# COMMUNICATION_INTERFACE.net
KiCad netlist of a schematic drawn in Altium Designer
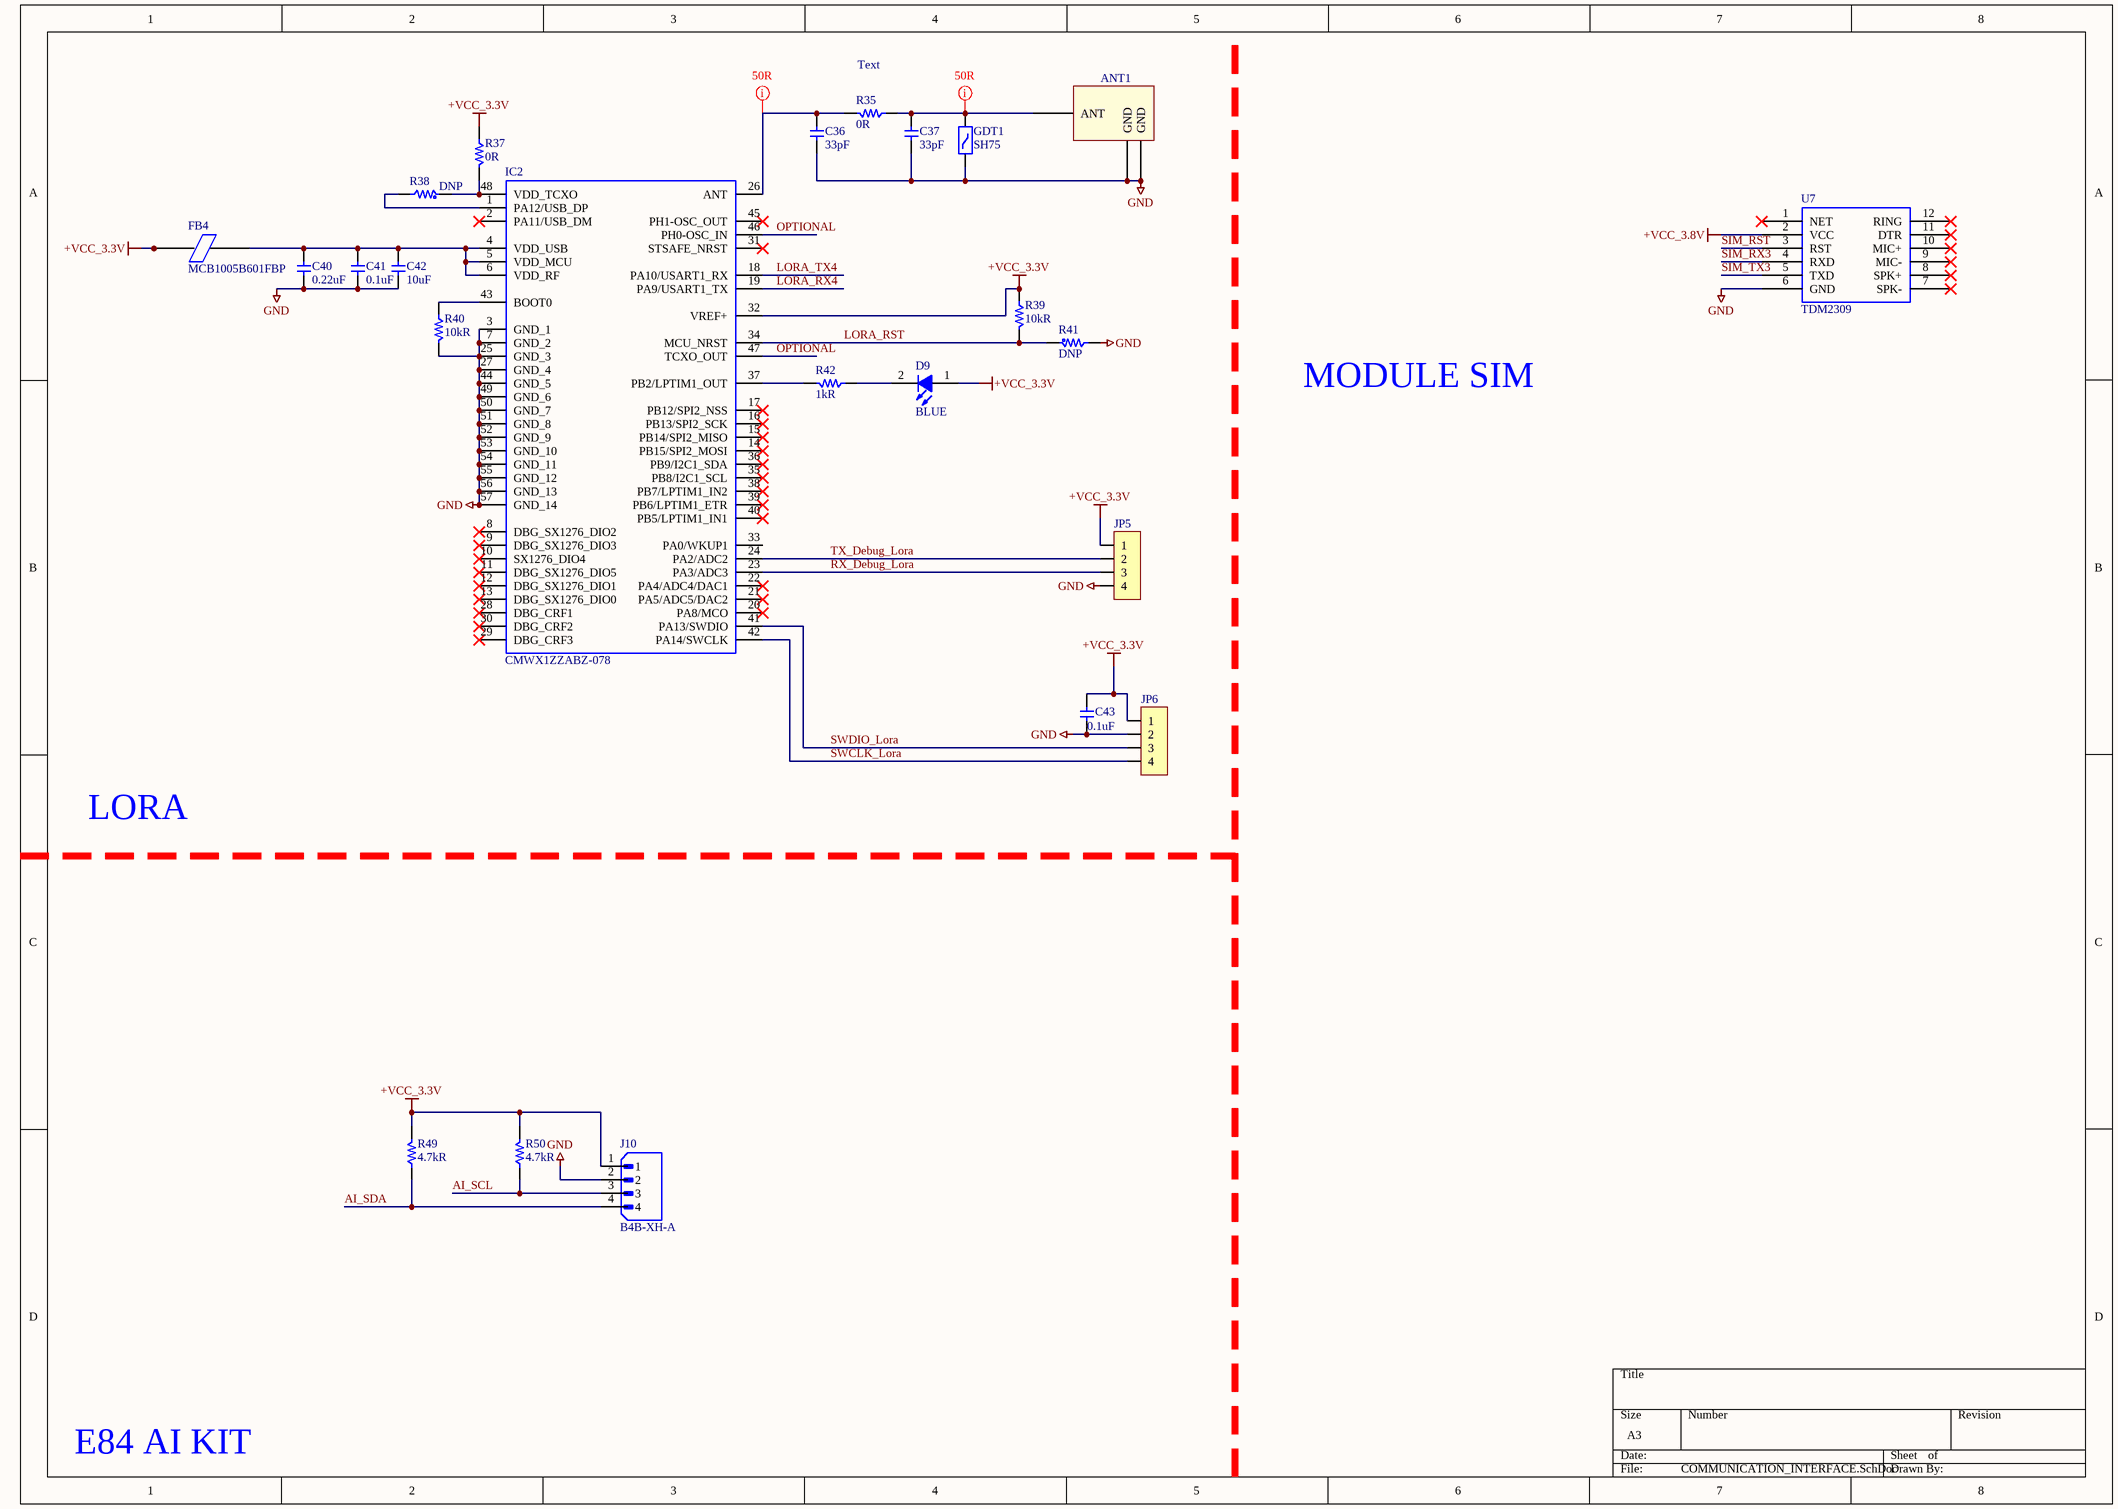
[diagram p0: COMMUNICATION_INTERFACE.SchDoc]

(export (version "E")
  (design (tool "Eeschema 10.0.6"))
  (components
    (comp (ref "ANT1")
      (value "Anten SMD")
      (footprint "20279-001E-01")
      (libsource (lib "BSR") (part "Antenna SMD"))
    )
    (comp (ref "C36")
      (value "33pF")
      (footprint "CAP 0402 (1005)")
      (description "50V 33pF NP0 ±5% 0402 Multilayer Ceramic Capacitors MLCC - SMD/SMT ROHS")
      (fields
        (field (name "MANUFACTURER") "YAGEO")
        (field (name "MANUFACTURER PART NUMBER") "CC0402JRNPO9BN330")
      )
      (libsource (lib "BSR NODE_V2.0 LIB") (part "CAP0402 33pF 50V"))
    )
    (comp (ref "C37")
      (value "33pF")
      (footprint "CAP 0402 (1005)")
      (description "50V 33pF NP0 ±5% 0402 Multilayer Ceramic Capacitors MLCC - SMD/SMT ROHS")
      (fields
        (field (name "MANUFACTURER") "YAGEO")
        (field (name "MANUFACTURER PART NUMBER") "CC0402JRNPO9BN330")
      )
      (libsource (lib "BSR NODE_V2.0 LIB") (part "CAP0402 33pF 50V"))
    )
    (comp (ref "C40")
      (value "0.22uF")
      (footprint "CAP 0402 (1005)")
      (description "35V 0.22uF X5R ±10% 0402 Multilayer Ceramic Capacitors MLCC - SMD/SMT ROHS")
      (fields
        (field (name "MANUFACTURER") "Murata Electronics")
        (field (name "MANUFACTURER PART NUMBER") "GRT155R6YA224KE01D")
      )
      (libsource (lib "BSR NODE_V2.0 LIB") (part "CAP0402 0.22uF 35V"))
    )
    (comp (ref "C41")
      (value "0.1uF")
      (footprint "CAP 0402 (1005)")
      (description "50V 100nF ±10% 0402 Multilayer Ceramic Capacitors MLCC - SMD/SMT ROHS")
      (fields
        (field (name "MANUFACTURER") "Samwha Capacitor")
        (field (name "MANUFACTURER PART NUMBER") "CS1005X7R104K500NR")
      )
      (libsource (lib "BSR NODE_V2.0 LIB") (part "CAP0402 0.1uF 50V"))
    )
    (comp (ref "C42")
      (value "10uF")
      (footprint "CAP 0603 (1608)")
      (description "25V 10uF X5R ±20% 0603 Multilayer Ceramic Capacitors MLCC - SMD/SMT ROHS")
      (fields
        (field (name "MANUFACTURER") "Chinocera")
        (field (name "MANUFACTURER PART NUMBER") "HGC0603R5106M250NTHJ")
      )
      (libsource (lib "BSR NODE_V2.0 LIB") (part "CAP0603 10uF 25V"))
    )
    (comp (ref "C43")
      (value "0.1uF")
      (footprint "CAP 0402 (1005)")
      (description "50V 100nF ±10% 0402 Multilayer Ceramic Capacitors MLCC - SMD/SMT ROHS")
      (fields
        (field (name "MANUFACTURER") "Samwha Capacitor")
        (field (name "MANUFACTURER PART NUMBER") "CS1005X7R104K500NR")
      )
      (libsource (lib "BSR NODE_V2.0 LIB") (part "CAP0402 0.1uF 50V"))
    )
    (comp (ref "D9")
      (value "BLUE")
      (footprint "LED0402 BLUE")
      (description "blue 0402 Light Emitting Diodes (LED) ROHS")
      (fields
        (field (name "MANUFACTURER") "BrtLed(Bright LED Elec)")
        (field (name "MANUFACTURER PART NUMBER") "BL-HB337A-AV-TRB")
      )
      (libsource (lib "BSR NODE_V2.0 LIB") (part "LED BLUE 0402"))
    )
    (comp (ref "FB4")
      (value "MCB1005B601FBP")
      (footprint "FB 0402 (1005)")
      (description "600mΩ ±25% 600Ω@100MHz 0402 Ferrite Beads ROHS")
      (fields (field (name "MANUFACTURER") "INPAQ"))
      (libsource (lib "BSR NODE_V2.0 LIB") (part "MCB1005B601FBP"))
    )
    (comp (ref "GDT1")
      (value "SH75")
      (footprint "GDT")
      (description "Gas Discharge Tube 75 V 5000A (5kA) 2 Pole Surface Mount")
      (fields (field (name "MANUFACTURER") "Littelfuse"))
      (libsource (lib "BSR NODE_V2.0 LIB") (part "GDT 75V 5KA 2 POLE SURFACE MOUNT"))
    )
    (comp (ref "IC2")
      (value "CMWX1ZZABZ-078")
      (footprint "CMWX1ZZABZ-078")
      (description "Integrated Circuit")
      (fields (field (name "MOUSER PART NUMBER") "81-CMWX1ZZABZ-078"))
      (libsource (lib "BSR") (part "CMWX1ZZABZ-078"))
    )
    (comp (ref "J10")
      (value "B4B-XH-A")
      (footprint "JST_B4B-XH-A")
      (description "Connector Header Through Hole 4 position 0.098 (2.50mm)")
      (fields (field (name "MF") "JST Sales"))
      (libsource (lib "B4B-XH-A") (part "B4B-XH-A"))
    )
    (comp (ref "JP5")
      (value "JP 1x4 2.54")
      (footprint "JP 1X4 DT")
      (description "Cắm")
      (libsource (lib "Altium_Lib_by_KhueNguyenCreator") (part "JP 1x4 2.54 Duc Thang"))
    )
    (comp (ref "JP6")
      (value "JP 1x4 2.54")
      (footprint "JP 1X4 DT")
      (description "Cắm")
      (libsource (lib "Altium_Lib_by_KhueNguyenCreator") (part "JP 1x4 2.54 Duc Thang"))
    )
    (comp (ref "R35")
      (value "0R")
      (footprint "RES 0603 (1608)")
      (description "0Ω 0603 Chip Resistor - Surface Mount ROHS")
      (fields
        (field (name "MANUFACTURER") "KOA Speer Elec")
        (field (name "MANUFACTURER PART NUMBER") "RK73Z1JTTD")
      )
      (libsource (lib "BSR NODE_V2.0 LIB") (part "RES0603 0R"))
    )
    (comp (ref "R37")
      (value "0R")
      (footprint "RES 0603 (1608)")
      (description "0Ω 0603 Chip Resistor - Surface Mount ROHS")
      (fields
        (field (name "MANUFACTURER") "KOA Speer Elec")
        (field (name "MANUFACTURER PART NUMBER") "RK73Z1JTTD")
      )
      (libsource (lib "BSR NODE_V2.0 LIB") (part "RES0603 0R"))
    )
    (comp (ref "R38")
      (value "DNP")
      (footprint "RES 0603 (1608)")
      (description "Res do not populate")
      (libsource (lib "BSR NODE_V2.0 LIB") (part "RES0603 DNP"))
    )
    (comp (ref "R39")
      (value "10kR")
      (footprint "RES 0402 (1005)")
      (description "±1% 10kΩ 0402 Chip Resistor - Surface Mount ROHS")
      (fields (field (name "MANUFACTURER") "VO") (field (name "MANUFACTURER PART NUMBER") "SCR0402F10K"))
      (libsource (lib "BSR NODE_V2.0 LIB") (part "RES0402 10kR 1%"))
    )
    (comp (ref "R40")
      (value "10kR")
      (footprint "RES 0402 (1005)")
      (description "±1% 10kΩ 0402 Chip Resistor - Surface Mount ROHS")
      (fields (field (name "MANUFACTURER") "VO") (field (name "MANUFACTURER PART NUMBER") "SCR0402F10K"))
      (libsource (lib "BSR NODE_V2.0 LIB") (part "RES0402 10kR 1%"))
    )
    (comp (ref "R41")
      (value "DNP")
      (footprint "RES 0402 (1005)")
      (description "Res do not populate")
      (libsource (lib "BSR NODE_V2.0 LIB") (part "RES0402 DNP"))
    )
    (comp (ref "R42")
      (value "1kR")
      (footprint "RES 0402 (1005)")
      (description "±5% 1kΩ 0402 Chip Resistor - Surface Mount ROHS")
      (fields (field (name "MANUFACTURER") "VO") (field (name "MANUFACTURER PART NUMBER") "SCR0402J1K"))
      (libsource (lib "BSR NODE_V2.0 LIB") (part "RES0402 1kR 1%"))
    )
    (comp (ref "R49")
      (value "4.7kR")
      (footprint "RES 0402 (1005)")
      (description "±5% 1kΩ 0402 Chip Resistor - Surface Mount ROHS")
      (fields (field (name "MANUFACTURER") "VO") (field (name "MANUFACTURER PART NUMBER") "SCR0402J1K"))
      (libsource (lib "BSR NODE_V2.0 LIB") (part "RES0402 1kR 1%"))
    )
    (comp (ref "R50")
      (value "4.7kR")
      (footprint "RES 0402 (1005)")
      (description "±5% 1kΩ 0402 Chip Resistor - Surface Mount ROHS")
      (fields (field (name "MANUFACTURER") "VO") (field (name "MANUFACTURER PART NUMBER") "SCR0402J1K"))
      (libsource (lib "BSR NODE_V2.0 LIB") (part "RES0402 1kR 1%"))
    )
    (comp (ref "U7")
      (value "TDM2309")
      (footprint "MODULE SIM SIM800L")
      (description "Module 4G SIMCOM A7680C TDM2309")
      (fields (field (name "MANUFACTURER") "SIMCOM"))
      (libsource (lib "BSR NODE_V2.0 LIB") (part "SIM TDM2309"))
    )
  )
  (nets
    (net (code "1") (name "+VCC_3.3V") (class "Default")
      (node (ref "C43") (pin "1") (pinfunction "1_1") (pintype "passive"))
      (node (ref "D9") (pin "1") (pinfunction "A_1") (pintype "passive"))
      (node (ref "FB4") (pin "1") (pinfunction "1_1") (pintype "passive"))
      (node (ref "IC2") (pin "32") (pinfunction "VREF+_32") (pintype "passive"))
      (node (ref "J10") (pin "1") (pinfunction "1_1") (pintype "passive"))
      (node (ref "JP5") (pin "1") (pinfunction "1_1") (pintype "passive"))
      (node (ref "JP6") (pin "1") (pinfunction "1_1") (pintype "passive"))
      (node (ref "R37") (pin "2") (pinfunction "2_2") (pintype "passive"))
      (node (ref "R39") (pin "2") (pinfunction "2_2") (pintype "passive"))
      (node (ref "R49") (pin "1") (pinfunction "1_1") (pintype "passive"))
      (node (ref "R50") (pin "1") (pinfunction "1_1") (pintype "passive"))
    )
    (net (code "2") (name "+VCC_3.8V") (class "Default")
      (node (ref "U7") (pin "2") (pinfunction "VCC_2") (pintype "passive"))
    )
    (net (code "3") (name "/AI_SCL") (class "Default")
      (node (ref "J10") (pin "3") (pinfunction "3_3") (pintype "passive"))
      (node (ref "R50") (pin "2") (pinfunction "2_2") (pintype "passive"))
    )
    (net (code "4") (name "/AI_SDA") (class "Default")
      (node (ref "J10") (pin "4") (pinfunction "4_4") (pintype "passive"))
      (node (ref "R49") (pin "2") (pinfunction "2_2") (pintype "passive"))
    )
    (net (code "5") (name "/LORA_RST") (class "Default")
      (node (ref "IC2") (pin "34") (pinfunction "MCU_NRST_34") (pintype "passive"))
      (node (ref "R39") (pin "1") (pinfunction "1_1") (pintype "passive"))
      (node (ref "R41") (pin "1") (pinfunction "1_1") (pintype "passive"))
    )
    (net (code "6") (name "/LORA_RX4") (class "Default")
      (node (ref "IC2") (pin "19") (pinfunction "PA9/USART1_TX_19") (pintype "passive"))
    )
    (net (code "7") (name "/LORA_TX4") (class "Default")
      (node (ref "IC2") (pin "18") (pinfunction "PA10/USART1_RX_18") (pintype "passive"))
    )
    (net (code "8") (name "/OPTIONAL") (class "Default")
      (node (ref "IC2") (pin "46") (pinfunction "PH0-OSC_IN_46") (pintype "passive"))
      (node (ref "IC2") (pin "47") (pinfunction "TCXO_OUT_47") (pintype "passive"))
    )
    (net (code "9") (name "/RX_Debug_Lora") (class "Default")
      (node (ref "IC2") (pin "23") (pinfunction "PA3/ADC3_23") (pintype "passive"))
      (node (ref "JP5") (pin "3") (pinfunction "3_3") (pintype "passive"))
    )
    (net (code "10") (name "/SIM_RST") (class "Default")
      (node (ref "U7") (pin "3") (pinfunction "RST_3") (pintype "passive"))
    )
    (net (code "11") (name "/SIM_RX3") (class "Default")
      (node (ref "U7") (pin "4") (pinfunction "RXD_4") (pintype "passive"))
    )
    (net (code "12") (name "/SIM_TX3") (class "Default")
      (node (ref "U7") (pin "5") (pinfunction "TXD_5") (pintype "passive"))
    )
    (net (code "13") (name "/SWCLK_Lora") (class "Default")
      (node (ref "IC2") (pin "42") (pinfunction "PA14/SWCLK_42") (pintype "passive"))
      (node (ref "JP6") (pin "4") (pinfunction "4_4") (pintype "passive"))
    )
    (net (code "14") (name "/SWDIO_Lora") (class "Default")
      (node (ref "IC2") (pin "41") (pinfunction "PA13/SWDIO_41") (pintype "passive"))
      (node (ref "JP6") (pin "3") (pinfunction "3_3") (pintype "passive"))
    )
    (net (code "15") (name "/TX_Debug_Lora") (class "Default")
      (node (ref "IC2") (pin "24") (pinfunction "PA2/ADC2_24") (pintype "passive"))
      (node (ref "JP5") (pin "2") (pinfunction "2_2") (pintype "passive"))
    )
    (net (code "16") (name "GND") (class "Default")
      (node (ref "ANT1") (pin "1") (pinfunction "GND_1") (pintype "passive"))
      (node (ref "ANT1") (pin "3") (pinfunction "GND_3") (pintype "passive"))
      (node (ref "C36") (pin "2") (pinfunction "2_2") (pintype "passive"))
      (node (ref "C37") (pin "2") (pinfunction "2_2") (pintype "passive"))
      (node (ref "C40") (pin "2") (pinfunction "2_2") (pintype "passive"))
      (node (ref "C41") (pin "2") (pinfunction "2_2") (pintype "passive"))
      (node (ref "C42") (pin "2") (pinfunction "2_2") (pintype "passive"))
      (node (ref "C43") (pin "2") (pinfunction "2_2") (pintype "passive"))
      (node (ref "GDT1") (pin "1") (pinfunction "1_1") (pintype "passive"))
      (node (ref "IC2") (pin "25") (pinfunction "GND_3_25") (pintype "passive"))
      (node (ref "IC2") (pin "27") (pinfunction "GND_4_27") (pintype "passive"))
      (node (ref "IC2") (pin "3") (pinfunction "GND_1_3") (pintype "passive"))
      (node (ref "IC2") (pin "44") (pinfunction "GND_5_44") (pintype "passive"))
      (node (ref "IC2") (pin "49") (pinfunction "GND_6_49") (pintype "passive"))
      (node (ref "IC2") (pin "50") (pinfunction "GND_7_50") (pintype "passive"))
      (node (ref "IC2") (pin "51") (pinfunction "GND_8_51") (pintype "passive"))
      (node (ref "IC2") (pin "52") (pinfunction "GND_9_52") (pintype "passive"))
      (node (ref "IC2") (pin "53") (pinfunction "GND_10_53") (pintype "passive"))
      (node (ref "IC2") (pin "54") (pinfunction "GND_11_54") (pintype "passive"))
      (node (ref "IC2") (pin "55") (pinfunction "GND_12_55") (pintype "passive"))
      (node (ref "IC2") (pin "56") (pinfunction "GND_13_56") (pintype "passive"))
      (node (ref "IC2") (pin "57") (pinfunction "GND_14_57") (pintype "passive"))
      (node (ref "IC2") (pin "7") (pinfunction "GND_2_7") (pintype "passive"))
      (node (ref "J10") (pin "2") (pinfunction "2_2") (pintype "passive"))
      (node (ref "JP5") (pin "4") (pinfunction "4_4") (pintype "passive"))
      (node (ref "JP6") (pin "2") (pinfunction "2_2") (pintype "passive"))
      (node (ref "R40") (pin "1") (pinfunction "1_1") (pintype "passive"))
      (node (ref "R41") (pin "2") (pinfunction "2_2") (pintype "passive"))
      (node (ref "U7") (pin "6") (pinfunction "GND_6") (pintype "passive"))
    )
    (net (code "17") (name "Net-(ANT1-ANT)") (class "Default")
      (node (ref "ANT1") (pin "2") (pinfunction "ANT_2") (pintype "passive"))
      (node (ref "C37") (pin "1") (pinfunction "1_1") (pintype "passive"))
      (node (ref "GDT1") (pin "2") (pinfunction "2_2") (pintype "passive"))
      (node (ref "R35") (pin "2") (pinfunction "2_2") (pintype "passive"))
    )
    (net (code "18") (name "Net-(D9-K)") (class "Default")
      (node (ref "D9") (pin "2") (pinfunction "K_2") (pintype "passive"))
      (node (ref "R42") (pin "2") (pinfunction "2_2") (pintype "passive"))
    )
    (net (code "19") (name "Net-(IC2-ANT)") (class "Default")
      (node (ref "C36") (pin "1") (pinfunction "1_1") (pintype "passive"))
      (node (ref "IC2") (pin "26") (pinfunction "ANT_26") (pintype "passive"))
      (node (ref "R35") (pin "1") (pinfunction "1_1") (pintype "passive"))
    )
    (net (code "20") (name "Net-(IC2-BOOT0)") (class "Default")
      (node (ref "IC2") (pin "43") (pinfunction "BOOT0_43") (pintype "passive"))
      (node (ref "R40") (pin "2") (pinfunction "2_2") (pintype "passive"))
    )
    (net (code "21") (name "Net-(IC2-PA12{slash}USB_DP)") (class "Default")
      (node (ref "IC2") (pin "1") (pinfunction "PA12/USB_DP_1") (pintype "passive"))
      (node (ref "R38") (pin "2") (pinfunction "2_2") (pintype "passive"))
    )
    (net (code "22") (name "Net-(IC2-PB2{slash}LPTIM1_OUT)") (class "Default")
      (node (ref "IC2") (pin "37") (pinfunction "PB2/LPTIM1_OUT_37") (pintype "passive"))
      (node (ref "R42") (pin "1") (pinfunction "1_1") (pintype "passive"))
    )
    (net (code "23") (name "Net-(IC2-VDD_MCU)") (class "Default")
      (node (ref "C40") (pin "1") (pinfunction "1_1") (pintype "passive"))
      (node (ref "C41") (pin "1") (pinfunction "1_1") (pintype "passive"))
      (node (ref "C42") (pin "1") (pinfunction "1_1") (pintype "passive"))
      (node (ref "FB4") (pin "2") (pinfunction "2_2") (pintype "passive"))
      (node (ref "IC2") (pin "4") (pinfunction "VDD_USB_4") (pintype "passive"))
      (node (ref "IC2") (pin "5") (pinfunction "VDD_MCU_5") (pintype "passive"))
      (node (ref "IC2") (pin "6") (pinfunction "VDD_RF_6") (pintype "passive"))
    )
    (net (code "24") (name "Net-(IC2-VDD_TCXO)") (class "Default")
      (node (ref "IC2") (pin "48") (pinfunction "VDD_TCXO_48") (pintype "passive"))
      (node (ref "R37") (pin "1") (pinfunction "1_1") (pintype "passive"))
      (node (ref "R38") (pin "1") (pinfunction "1_1") (pintype "passive"))
    )
    (net (code "25") (name "unconnected-(IC2-DBG_CRF1-Pad28)") (class "Default")
      (node (ref "IC2") (pin "28") (pinfunction "DBG_CRF1_28") (pintype "passive+no_connect"))
    )
    (net (code "26") (name "unconnected-(IC2-DBG_CRF2-Pad30)") (class "Default")
      (node (ref "IC2") (pin "30") (pinfunction "DBG_CRF2_30") (pintype "passive+no_connect"))
    )
    (net (code "27") (name "unconnected-(IC2-DBG_CRF3-Pad29)") (class "Default")
      (node (ref "IC2") (pin "29") (pinfunction "DBG_CRF3_29") (pintype "passive+no_connect"))
    )
    (net (code "28") (name "unconnected-(IC2-DBG_SX1276_DIO0-Pad13)") (class "Default")
      (node (ref "IC2") (pin "13") (pinfunction "DBG_SX1276_DIO0_13") (pintype "passive+no_connect"))
    )
    (net (code "29") (name "unconnected-(IC2-DBG_SX1276_DIO1-Pad12)") (class "Default")
      (node (ref "IC2") (pin "12") (pinfunction "DBG_SX1276_DIO1_12") (pintype "passive+no_connect"))
    )
    (net (code "30") (name "unconnected-(IC2-DBG_SX1276_DIO2-Pad8)") (class "Default")
      (node (ref "IC2") (pin "8") (pinfunction "DBG_SX1276_DIO2_8") (pintype "passive+no_connect"))
    )
    (net (code "31") (name "unconnected-(IC2-DBG_SX1276_DIO3-Pad9)") (class "Default")
      (node (ref "IC2") (pin "9") (pinfunction "DBG_SX1276_DIO3_9") (pintype "passive+no_connect"))
    )
    (net (code "32") (name "unconnected-(IC2-DBG_SX1276_DIO5-Pad11)") (class "Default")
      (node (ref "IC2") (pin "11") (pinfunction "DBG_SX1276_DIO5_11") (pintype "passive+no_connect"))
    )
    (net (code "33") (name "unconnected-(IC2-PA0{slash}WKUP1-Pad33)") (class "Default")
      (node (ref "IC2") (pin "33") (pinfunction "PA0/WKUP1_33") (pintype "passive"))
    )
    (net (code "34") (name "unconnected-(IC2-PA4{slash}ADC4{slash}DAC1-Pad22)") (class "Default")
      (node (ref "IC2") (pin "22") (pinfunction "PA4/ADC4/DAC1_22") (pintype "passive+no_connect"))
    )
    (net (code "35") (name "unconnected-(IC2-PA5{slash}ADC5{slash}DAC2-Pad21)") (class "Default")
      (node (ref "IC2") (pin "21") (pinfunction "PA5/ADC5/DAC2_21") (pintype "passive+no_connect"))
    )
    (net (code "36") (name "unconnected-(IC2-PA8{slash}MCO-Pad20)") (class "Default")
      (node (ref "IC2") (pin "20") (pinfunction "PA8/MCO_20") (pintype "passive+no_connect"))
    )
    (net (code "37") (name "unconnected-(IC2-PA11{slash}USB_DM-Pad2)") (class "Default")
      (node (ref "IC2") (pin "2") (pinfunction "PA11/USB_DM_2") (pintype "passive+no_connect"))
    )
    (net (code "38") (name "unconnected-(IC2-PB5{slash}LPTIM1_IN1-Pad40)") (class "Default")
      (node (ref "IC2") (pin "40") (pinfunction "PB5/LPTIM1_IN1_40") (pintype "passive+no_connect"))
    )
    (net (code "39") (name "unconnected-(IC2-PB6{slash}LPTIM1_ETR-Pad39)") (class "Default")
      (node (ref "IC2") (pin "39") (pinfunction "PB6/LPTIM1_ETR_39") (pintype "passive+no_connect"))
    )
    (net (code "40") (name "unconnected-(IC2-PB7{slash}LPTIM1_IN2-Pad38)") (class "Default")
      (node (ref "IC2") (pin "38") (pinfunction "PB7/LPTIM1_IN2_38") (pintype "passive+no_connect"))
    )
    (net (code "41") (name "unconnected-(IC2-PB8{slash}I2C1_SCL-Pad35)") (class "Default")
      (node (ref "IC2") (pin "35") (pinfunction "PB8/I2C1_SCL_35") (pintype "passive+no_connect"))
    )
    (net (code "42") (name "unconnected-(IC2-PB9{slash}I2C1_SDA-Pad36)") (class "Default")
      (node (ref "IC2") (pin "36") (pinfunction "PB9/I2C1_SDA_36") (pintype "passive+no_connect"))
    )
    (net (code "43") (name "unconnected-(IC2-PB12{slash}SPI2_NSS-Pad17)") (class "Default")
      (node (ref "IC2") (pin "17") (pinfunction "PB12/SPI2_NSS_17") (pintype "passive+no_connect"))
    )
    (net (code "44") (name "unconnected-(IC2-PB13{slash}SPI2_SCK-Pad16)") (class "Default")
      (node (ref "IC2") (pin "16") (pinfunction "PB13/SPI2_SCK_16") (pintype "passive+no_connect"))
    )
    (net (code "45") (name "unconnected-(IC2-PB14{slash}SPI2_MISO-Pad15)") (class "Default")
      (node (ref "IC2") (pin "15") (pinfunction "PB14/SPI2_MISO_15") (pintype "passive+no_connect"))
    )
    (net (code "46") (name "unconnected-(IC2-PB15{slash}SPI2_MOSI-Pad14)") (class "Default")
      (node (ref "IC2") (pin "14") (pinfunction "PB15/SPI2_MOSI_14") (pintype "passive+no_connect"))
    )
    (net (code "47") (name "unconnected-(IC2-PH1-OSC_OUT-Pad45)") (class "Default")
      (node (ref "IC2") (pin "45") (pinfunction "PH1-OSC_OUT_45") (pintype "passive+no_connect"))
    )
    (net (code "48") (name "unconnected-(IC2-STSAFE_NRST-Pad31)") (class "Default")
      (node (ref "IC2") (pin "31") (pinfunction "STSAFE_NRST_31") (pintype "passive+no_connect"))
    )
    (net (code "49") (name "unconnected-(IC2-SX1276_DIO4-Pad10)") (class "Default")
      (node (ref "IC2") (pin "10") (pinfunction "SX1276_DIO4_10") (pintype "passive+no_connect"))
    )
    (net (code "50") (name "unconnected-(U7-DTR-Pad11)") (class "Default")
      (node (ref "U7") (pin "11") (pinfunction "DTR_11") (pintype "passive+no_connect"))
    )
    (net (code "51") (name "unconnected-(U7-MIC+-Pad10)") (class "Default")
      (node (ref "U7") (pin "10") (pinfunction "MIC+_10") (pintype "passive+no_connect"))
    )
    (net (code "52") (name "unconnected-(U7-MIC--Pad9)") (class "Default")
      (node (ref "U7") (pin "9") (pinfunction "MIC-_9") (pintype "passive+no_connect"))
    )
    (net (code "53") (name "unconnected-(U7-NET-Pad1)") (class "Default")
      (node (ref "U7") (pin "1") (pinfunction "NET_1") (pintype "passive+no_connect"))
    )
    (net (code "54") (name "unconnected-(U7-RING-Pad12)") (class "Default")
      (node (ref "U7") (pin "12") (pinfunction "RING_12") (pintype "passive+no_connect"))
    )
    (net (code "55") (name "unconnected-(U7-SPK+-Pad8)") (class "Default")
      (node (ref "U7") (pin "8") (pinfunction "SPK+_8") (pintype "passive+no_connect"))
    )
    (net (code "56") (name "unconnected-(U7-SPK--Pad7)") (class "Default")
      (node (ref "U7") (pin "7") (pinfunction "SPK-_7") (pintype "passive+no_connect"))
    )
  )
)
